# timer.net
KiCad netlist of a schematic drawn in EAGLE
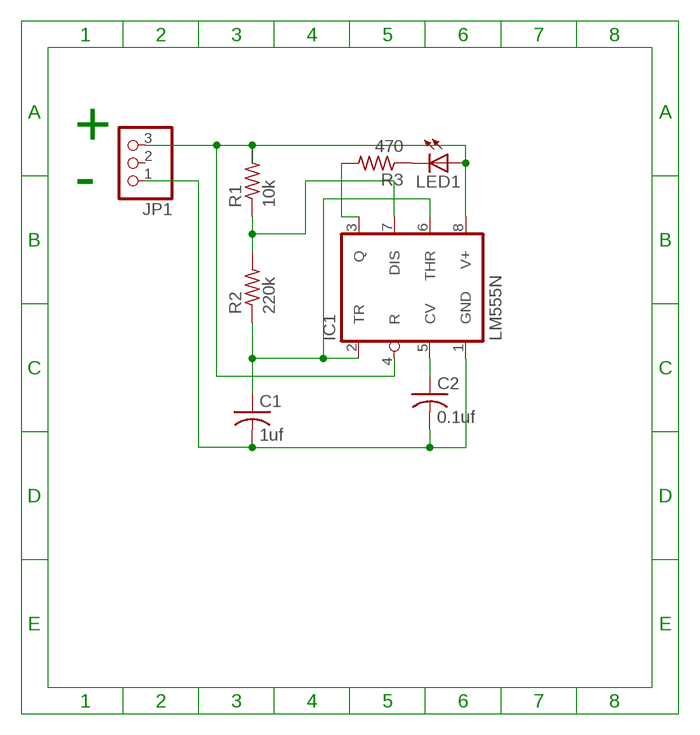
[diagram p0: schematic, sheet 1]

(export (version "E")
  (design (tool "Eeschema 10.0.6"))
  (components
    (comp (ref "C1")
      (value "1uf")
      (footprint "eagle-import:C050-025X075")
      (libsource (lib "eagle-import") (part "C-US050-025X075"))
    )
    (comp (ref "C2")
      (value "0.1uf")
      (footprint "eagle-import:C050-025X075")
      (libsource (lib "eagle-import") (part "C-US050-025X075"))
    )
    (comp (ref "IC1")
      (value "LM555N")
      (footprint "eagle-import:DIL08-ROUND")
      (libsource (lib "eagle-import") (part "555NLM"))
    )
    (comp (ref "JP1")
      (value "PINHD-1X3")
      (footprint "eagle-import:1X03")
      (libsource (lib "eagle-import") (part "PINHD-1X3"))
    )
    (comp (ref "LED1")
      (value "LED5MM")
      (footprint "eagle-import:LED5MM")
      (libsource (lib "eagle-import") (part "LED5MM"))
    )
    (comp (ref "R1")
      (value "10k")
      (footprint "eagle-import:0309_10")
      (libsource (lib "eagle-import") (part "R-US_0309/10"))
    )
    (comp (ref "R2")
      (value "220k")
      (footprint "eagle-import:0309_10")
      (libsource (lib "eagle-import") (part "R-US_0309/10"))
    )
    (comp (ref "R3")
      (value "470")
      (footprint "eagle-import:0309_10")
      (libsource (lib "eagle-import") (part "R-US_0309/10"))
    )
  )
  (nets
    (net (code "1") (name "Net-(IC1-CV)") (class "Default")
      (node (ref "C2") (pin "1") (pinfunction "1_1") (pintype "passive"))
      (node (ref "IC1") (pin "5") (pinfunction "CV_5") (pintype "input"))
    )
    (net (code "2") (name "Net-(IC1-DIS)") (class "Default")
      (node (ref "IC1") (pin "7") (pinfunction "DIS_7") (pintype "input"))
      (node (ref "R1") (pin "1") (pinfunction "1_1") (pintype "passive"))
      (node (ref "R2") (pin "2") (pinfunction "2_2") (pintype "passive"))
    )
    (net (code "3") (name "Net-(IC1-GND)") (class "Default")
      (node (ref "C1") (pin "2") (pinfunction "2_2") (pintype "passive"))
      (node (ref "C2") (pin "2") (pinfunction "2_2") (pintype "passive"))
      (node (ref "IC1") (pin "1") (pinfunction "GND_1") (pintype "power_in"))
      (node (ref "JP1") (pin "1") (pinfunction "1_1") (pintype "passive"))
    )
    (net (code "4") (name "Net-(IC1-Q)") (class "Default")
      (node (ref "IC1") (pin "3") (pinfunction "Q_3") (pintype "output"))
      (node (ref "R3") (pin "2") (pinfunction "2_2") (pintype "passive"))
    )
    (net (code "5") (name "Net-(IC1-R)") (class "Default")
      (node (ref "IC1") (pin "4") (pinfunction "R_4") (pintype "input"))
      (node (ref "IC1") (pin "8") (pinfunction "V+_8") (pintype "power_in"))
      (node (ref "JP1") (pin "3") (pinfunction "3_3") (pintype "passive"))
      (node (ref "LED1") (pin "A") (pinfunction "A_A") (pintype "passive"))
      (node (ref "R1") (pin "2") (pinfunction "2_2") (pintype "passive"))
    )
    (net (code "6") (name "Net-(IC1-THR)") (class "Default")
      (node (ref "C1") (pin "1") (pinfunction "1_1") (pintype "passive"))
      (node (ref "IC1") (pin "2") (pinfunction "TR_2") (pintype "input"))
      (node (ref "IC1") (pin "6") (pinfunction "THR_6") (pintype "input"))
      (node (ref "R2") (pin "1") (pinfunction "1_1") (pintype "passive"))
    )
    (net (code "7") (name "Net-(LED1-C)") (class "Default")
      (node (ref "LED1") (pin "K") (pinfunction "C_K") (pintype "passive"))
      (node (ref "R3") (pin "1") (pinfunction "1_1") (pintype "passive"))
    )
    (net (code "8") (name "unconnected-(JP1-Pad2)") (class "Default")
      (node (ref "JP1") (pin "2") (pinfunction "2_2") (pintype "passive"))
    )
  )
)
